# untitled.net
KiCad netlist of a schematic drawn in EAGLE
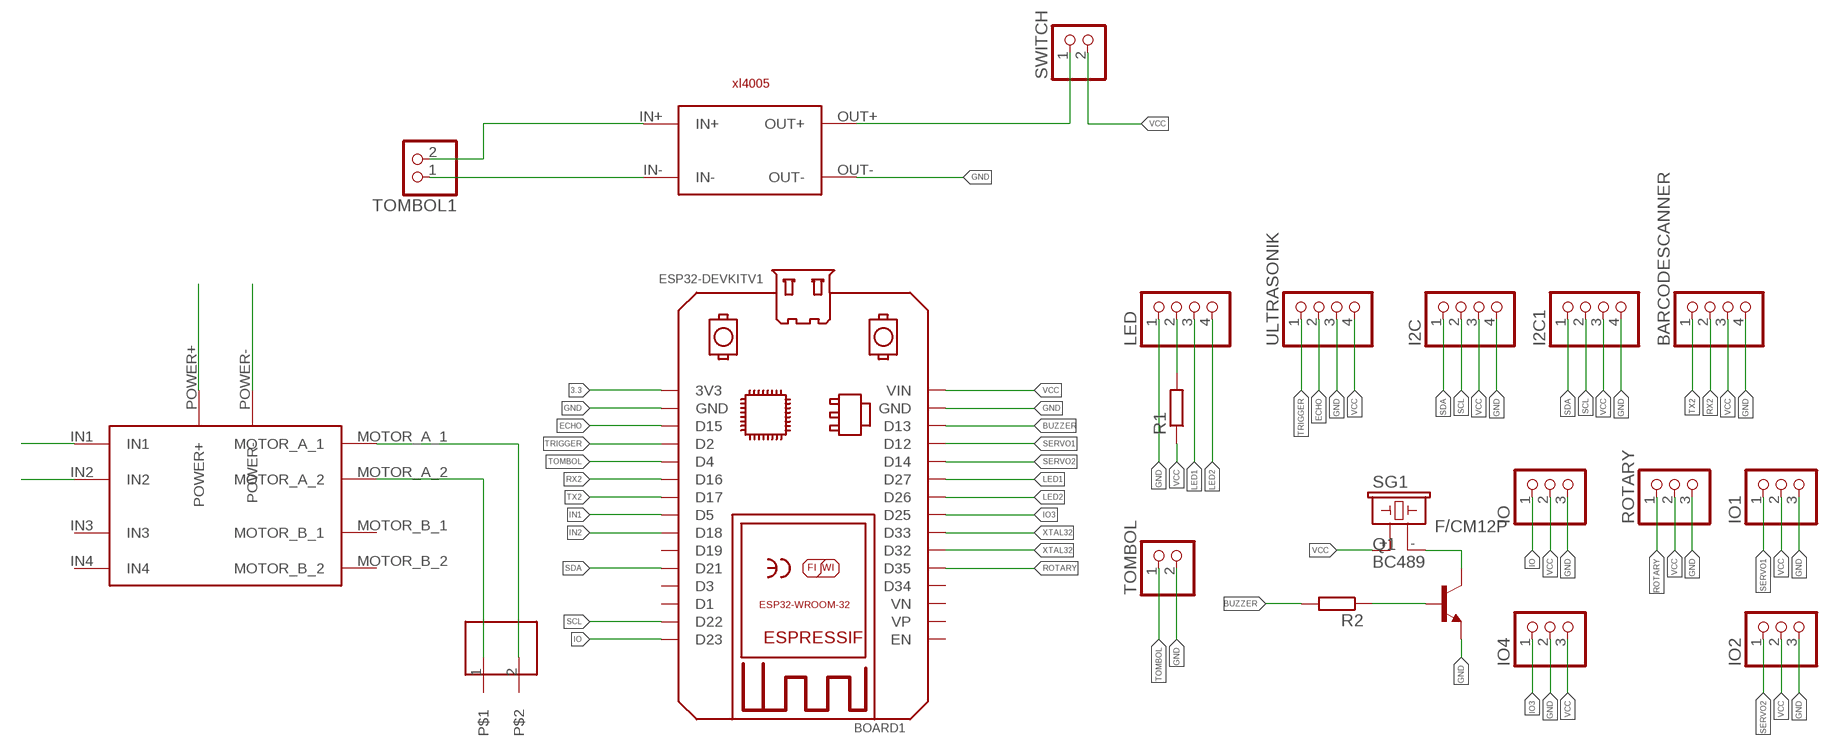
[diagram p0: schematic, sheet 1]

(export (version "E")
  (design (tool "Eeschema 10.0.6"))
  (components
    (comp (ref "BARCODESCANNER")
      (value "PINHD-1X4")
      (footprint "eagle-import:1X04")
      (libsource (lib "eagle-import") (part "PINHD-1X4"))
    )
    (comp (ref "BOARD1")
      (value "ESP32DEVKITV1SHRIDATTDUDHAT")
      (footprint "eagle-import:ESP32-DEVKITV1")
      (libsource (lib "eagle-import") (part "ESP32DEVKITV1SHRIDATTDUDHAT"))
    )
    (comp (ref "I2C")
      (value "PINHD-1X4")
      (footprint "eagle-import:1X04")
      (libsource (lib "eagle-import") (part "PINHD-1X4"))
    )
    (comp (ref "I2C1")
      (value "PINHD-1X4")
      (footprint "eagle-import:1X04")
      (libsource (lib "eagle-import") (part "PINHD-1X4"))
    )
    (comp (ref "IO")
      (value "PINHD-1X3")
      (footprint "eagle-import:1X03")
      (libsource (lib "eagle-import") (part "PINHD-1X3"))
    )
    (comp (ref "IO1")
      (value "PINHD-1X3")
      (footprint "eagle-import:1X03")
      (libsource (lib "eagle-import") (part "PINHD-1X3"))
    )
    (comp (ref "IO2")
      (value "PINHD-1X3")
      (footprint "eagle-import:1X03")
      (libsource (lib "eagle-import") (part "PINHD-1X3"))
    )
    (comp (ref "IO4")
      (value "PINHD-1X3")
      (footprint "eagle-import:1X03")
      (libsource (lib "eagle-import") (part "PINHD-1X3"))
    )
    (comp (ref "LED")
      (value "PINHD-1X4")
      (footprint "eagle-import:1X04")
      (libsource (lib "eagle-import") (part "PINHD-1X4"))
    )
    (comp (ref "Q1")
      (value "BC489")
      (footprint "eagle-import:TO92-EBC")
      (libsource (lib "eagle-import") (part "BC489"))
    )
    (comp (ref "R1")
      (value "R-EU_0207/10")
      (footprint "eagle-import:0207_10")
      (libsource (lib "eagle-import") (part "R-EU_0207/10"))
    )
    (comp (ref "R2")
      (value "R-EU_0207/10")
      (footprint "eagle-import:0207_10")
      (libsource (lib "eagle-import") (part "R-EU_0207/10"))
    )
    (comp (ref "ROTARY")
      (value "PINHD-1X3")
      (footprint "eagle-import:1X03")
      (libsource (lib "eagle-import") (part "PINHD-1X3"))
    )
    (comp (ref "SG1")
      (value "F/CM12P")
      (footprint "eagle-import:F_CM12P")
      (libsource (lib "eagle-import") (part "F/CM12P"))
    )
    (comp (ref "SWITCH")
      (value "PINHD-1X2")
      (footprint "eagle-import:1X02")
      (libsource (lib "eagle-import") (part "PINHD-1X2"))
    )
    (comp (ref "TOMBOL")
      (value "PINHD-1X2")
      (footprint "eagle-import:1X02")
      (libsource (lib "eagle-import") (part "PINHD-1X2"))
    )
    (comp (ref "TOMBOL1")
      (value "PINHD-1X2")
      (footprint "eagle-import:1X02")
      (libsource (lib "eagle-import") (part "PINHD-1X2"))
    )
    (comp (ref "U$1")
      (value "DRIVERMOTOR_MINI")
      (footprint "eagle-import:DRIVERMOTOR_MINI")
      (libsource (lib "eagle-import") (part "DRIVERMOTOR_MINI"))
    )
    (comp (ref "U$2")
      (value "DC-STEP-DOWN-XL4005")
      (footprint "eagle-import:DC-STEP-DOWN-XL4005")
      (libsource (lib "eagle-import") (part "DC-STEP-DOWN-XL4005"))
    )
    (comp (ref "U$3")
      (value "TERMINALBLOCK2")
      (footprint "eagle-import:TERMINALBLOCK2")
      (libsource (lib "eagle-import") (part "TERMINALBLOCK2"))
    )
    (comp (ref "ULTRASONIK")
      (value "PINHD-1X4")
      (footprint "eagle-import:1X04")
      (libsource (lib "eagle-import") (part "PINHD-1X4"))
    )
  )
  (nets
    (net (code "1") (name "3.3") (class "Default")
      (node (ref "BOARD1") (pin "3V3") (pinfunction "3V3_3V3") (pintype "bidirectional"))
    )
    (net (code "2") (name "BUZZER") (class "Default")
      (node (ref "BOARD1") (pin "D13") (pinfunction "D13_D13") (pintype "bidirectional"))
      (node (ref "R2") (pin "2") (pinfunction "2_2") (pintype "passive"))
    )
    (net (code "3") (name "ECHO") (class "Default")
      (node (ref "BOARD1") (pin "D15") (pinfunction "D15_D15") (pintype "bidirectional"))
      (node (ref "ULTRASONIK") (pin "2") (pinfunction "2_2") (pintype "passive"))
    )
    (net (code "4") (name "GND") (class "Default")
      (node (ref "BARCODESCANNER") (pin "4") (pinfunction "4_4") (pintype "passive"))
      (node (ref "BOARD1") (pin "GND") (pinfunction "GND_GND") (pintype "bidirectional"))
      (node (ref "BOARD1") (pin "GND@1") (pinfunction "GND_GND@1") (pintype "bidirectional"))
      (node (ref "I2C") (pin "4") (pinfunction "4_4") (pintype "passive"))
      (node (ref "I2C1") (pin "4") (pinfunction "4_4") (pintype "passive"))
      (node (ref "IO") (pin "3") (pinfunction "3_3") (pintype "passive"))
      (node (ref "IO1") (pin "3") (pinfunction "3_3") (pintype "passive"))
      (node (ref "IO2") (pin "3") (pinfunction "3_3") (pintype "passive"))
      (node (ref "IO4") (pin "2") (pinfunction "2_2") (pintype "passive"))
      (node (ref "LED") (pin "1") (pinfunction "1_1") (pintype "passive"))
      (node (ref "Q1") (pin "E") (pinfunction "E_E") (pintype "passive"))
      (node (ref "ROTARY") (pin "3") (pinfunction "3_3") (pintype "passive"))
      (node (ref "TOMBOL") (pin "2") (pinfunction "2_2") (pintype "passive"))
      (node (ref "U$1") (pin "POWER-") (pinfunction "POWER-_POWER-") (pintype "bidirectional"))
      (node (ref "U$2") (pin "OUT-") (pinfunction "OUT-_OUT-") (pintype "bidirectional"))
      (node (ref "ULTRASONIK") (pin "3") (pinfunction "3_3") (pintype "passive"))
    )
    (net (code "5") (name "IN1") (class "Default")
      (node (ref "BOARD1") (pin "D5") (pinfunction "D5_D5") (pintype "bidirectional"))
      (node (ref "U$1") (pin "IN1") (pinfunction "IN1_IN1") (pintype "bidirectional"))
    )
    (net (code "6") (name "IN2") (class "Default")
      (node (ref "BOARD1") (pin "D18") (pinfunction "D18_D18") (pintype "bidirectional"))
      (node (ref "U$1") (pin "IN2") (pinfunction "IN2_IN2") (pintype "bidirectional"))
    )
    (net (code "7") (name "IO") (class "Default")
      (node (ref "BOARD1") (pin "D23") (pinfunction "D23_D23") (pintype "bidirectional"))
      (node (ref "IO") (pin "1") (pinfunction "1_1") (pintype "passive"))
    )
    (net (code "8") (name "IO3") (class "Default")
      (node (ref "BOARD1") (pin "D25") (pinfunction "D25_D25") (pintype "bidirectional"))
      (node (ref "IO4") (pin "1") (pinfunction "1_1") (pintype "passive"))
    )
    (net (code "9") (name "LED1") (class "Default")
      (node (ref "BOARD1") (pin "D27") (pinfunction "D27_D27") (pintype "bidirectional"))
      (node (ref "LED") (pin "3") (pinfunction "3_3") (pintype "passive"))
    )
    (net (code "10") (name "LED2") (class "Default")
      (node (ref "BOARD1") (pin "D26") (pinfunction "D26_D26") (pintype "bidirectional"))
      (node (ref "LED") (pin "4") (pinfunction "4_4") (pintype "passive"))
    )
    (net (code "11") (name "Net-(LED-Pad2)") (class "Default")
      (node (ref "LED") (pin "2") (pinfunction "2_2") (pintype "passive"))
      (node (ref "R1") (pin "2") (pinfunction "2_2") (pintype "passive"))
    )
    (net (code "12") (name "Net-(Q1-PadB)") (class "Default")
      (node (ref "Q1") (pin "B") (pinfunction "B_B") (pintype "passive"))
      (node (ref "R2") (pin "1") (pinfunction "1_1") (pintype "passive"))
    )
    (net (code "13") (name "Net-(SG1-2)") (class "Default")
      (node (ref "Q1") (pin "C") (pinfunction "C_C") (pintype "passive"))
      (node (ref "SG1") (pin "-") (pinfunction "2_-") (pintype "passive"))
    )
    (net (code "14") (name "Net-(SWITCH-Pad1)") (class "Default")
      (node (ref "SWITCH") (pin "1") (pinfunction "1_1") (pintype "passive"))
      (node (ref "U$2") (pin "OUT+") (pinfunction "OUT+_OUT+") (pintype "bidirectional"))
    )
    (net (code "15") (name "Net-(TOMBOL1-Pad1)") (class "Default")
      (node (ref "TOMBOL1") (pin "1") (pinfunction "1_1") (pintype "passive"))
      (node (ref "U$2") (pin "IN-") (pinfunction "IN-_IN-") (pintype "bidirectional"))
    )
    (net (code "16") (name "Net-(TOMBOL1-Pad2)") (class "Default")
      (node (ref "TOMBOL1") (pin "2") (pinfunction "2_2") (pintype "passive"))
      (node (ref "U$2") (pin "IN+") (pinfunction "IN+_IN+") (pintype "bidirectional"))
    )
    (net (code "17") (name "Net-(U$3-P$1)") (class "Default")
      (node (ref "U$1") (pin "MOTOR_A_2") (pinfunction "MOTOR_A_2_MOTOR_A_2") (pintype "bidirectional"))
      (node (ref "U$3") (pin "1") (pinfunction "P$1_1") (pintype "bidirectional"))
    )
    (net (code "18") (name "Net-(U$3-P$2)") (class "Default")
      (node (ref "U$1") (pin "MOTOR_A_1") (pinfunction "MOTOR_A_1_MOTOR_A_1") (pintype "bidirectional"))
      (node (ref "U$3") (pin "2") (pinfunction "P$2_2") (pintype "bidirectional"))
    )
    (net (code "19") (name "ROTARY") (class "Default")
      (node (ref "BOARD1") (pin "D35") (pinfunction "D35_D35") (pintype "bidirectional"))
      (node (ref "ROTARY") (pin "1") (pinfunction "1_1") (pintype "passive"))
    )
    (net (code "20") (name "RX2") (class "Default")
      (node (ref "BARCODESCANNER") (pin "2") (pinfunction "2_2") (pintype "passive"))
      (node (ref "BOARD1") (pin "D16") (pinfunction "D16_D16") (pintype "bidirectional"))
    )
    (net (code "21") (name "SCL") (class "Default")
      (node (ref "BOARD1") (pin "D22") (pinfunction "D22_D22") (pintype "bidirectional"))
      (node (ref "I2C") (pin "2") (pinfunction "2_2") (pintype "passive"))
      (node (ref "I2C1") (pin "2") (pinfunction "2_2") (pintype "passive"))
    )
    (net (code "22") (name "SDA") (class "Default")
      (node (ref "BOARD1") (pin "D21") (pinfunction "D21_D21") (pintype "bidirectional"))
      (node (ref "I2C") (pin "1") (pinfunction "1_1") (pintype "passive"))
      (node (ref "I2C1") (pin "1") (pinfunction "1_1") (pintype "passive"))
    )
    (net (code "23") (name "SERVO1") (class "Default")
      (node (ref "BOARD1") (pin "D12") (pinfunction "D12_D12") (pintype "bidirectional"))
      (node (ref "IO1") (pin "1") (pinfunction "1_1") (pintype "passive"))
    )
    (net (code "24") (name "SERVO2") (class "Default")
      (node (ref "BOARD1") (pin "D14") (pinfunction "D14_D14") (pintype "bidirectional"))
      (node (ref "IO2") (pin "1") (pinfunction "1_1") (pintype "passive"))
    )
    (net (code "25") (name "TOMBOL") (class "Default")
      (node (ref "BOARD1") (pin "D4") (pinfunction "D4_D4") (pintype "bidirectional"))
      (node (ref "TOMBOL") (pin "1") (pinfunction "1_1") (pintype "passive"))
    )
    (net (code "26") (name "TRIGGER") (class "Default")
      (node (ref "BOARD1") (pin "D2") (pinfunction "D2_D2") (pintype "bidirectional"))
      (node (ref "ULTRASONIK") (pin "1") (pinfunction "1_1") (pintype "passive"))
    )
    (net (code "27") (name "TX2") (class "Default")
      (node (ref "BARCODESCANNER") (pin "1") (pinfunction "1_1") (pintype "passive"))
      (node (ref "BOARD1") (pin "D17") (pinfunction "D17_D17") (pintype "bidirectional"))
    )
    (net (code "28") (name "VCC") (class "Default")
      (node (ref "BARCODESCANNER") (pin "3") (pinfunction "3_3") (pintype "passive"))
      (node (ref "BOARD1") (pin "VIN") (pinfunction "VIN_VIN") (pintype "bidirectional"))
      (node (ref "I2C") (pin "3") (pinfunction "3_3") (pintype "passive"))
      (node (ref "I2C1") (pin "3") (pinfunction "3_3") (pintype "passive"))
      (node (ref "IO") (pin "2") (pinfunction "2_2") (pintype "passive"))
      (node (ref "IO1") (pin "2") (pinfunction "2_2") (pintype "passive"))
      (node (ref "IO2") (pin "2") (pinfunction "2_2") (pintype "passive"))
      (node (ref "IO4") (pin "3") (pinfunction "3_3") (pintype "passive"))
      (node (ref "R1") (pin "1") (pinfunction "1_1") (pintype "passive"))
      (node (ref "ROTARY") (pin "2") (pinfunction "2_2") (pintype "passive"))
      (node (ref "SG1") (pin "+") (pinfunction "1_+") (pintype "passive"))
      (node (ref "SWITCH") (pin "2") (pinfunction "2_2") (pintype "passive"))
      (node (ref "U$1") (pin "POWER+") (pinfunction "POWER+_POWER+") (pintype "bidirectional"))
      (node (ref "ULTRASONIK") (pin "4") (pinfunction "4_4") (pintype "passive"))
    )
    (net (code "29") (name "XTAL32") (class "Default")
      (node (ref "BOARD1") (pin "D32") (pinfunction "D32_D32") (pintype "bidirectional"))
      (node (ref "BOARD1") (pin "D33") (pinfunction "D33_D33") (pintype "bidirectional"))
    )
    (net (code "30") (name "unconnected-(BOARD1-PadD1)") (class "Default")
      (node (ref "BOARD1") (pin "D1") (pinfunction "D1_D1") (pintype "bidirectional"))
    )
    (net (code "31") (name "unconnected-(BOARD1-PadD3)") (class "Default")
      (node (ref "BOARD1") (pin "D3") (pinfunction "D3_D3") (pintype "bidirectional"))
    )
    (net (code "32") (name "unconnected-(BOARD1-PadD19)") (class "Default")
      (node (ref "BOARD1") (pin "D19") (pinfunction "D19_D19") (pintype "bidirectional"))
    )
    (net (code "33") (name "unconnected-(BOARD1-PadD34)") (class "Default")
      (node (ref "BOARD1") (pin "D34") (pinfunction "D34_D34") (pintype "bidirectional"))
    )
    (net (code "34") (name "unconnected-(BOARD1-PadEN)") (class "Default")
      (node (ref "BOARD1") (pin "EN") (pinfunction "EN_EN") (pintype "bidirectional"))
    )
    (net (code "35") (name "unconnected-(BOARD1-PadVN)") (class "Default")
      (node (ref "BOARD1") (pin "VN") (pinfunction "VN_VN") (pintype "bidirectional"))
    )
    (net (code "36") (name "unconnected-(BOARD1-PadVP)") (class "Default")
      (node (ref "BOARD1") (pin "VP") (pinfunction "VP_VP") (pintype "bidirectional"))
    )
    (net (code "37") (name "unconnected-(U$1-PadIN3)") (class "Default")
      (node (ref "U$1") (pin "IN3") (pinfunction "IN3_IN3") (pintype "bidirectional"))
    )
    (net (code "38") (name "unconnected-(U$1-PadIN4)") (class "Default")
      (node (ref "U$1") (pin "IN4") (pinfunction "IN4_IN4") (pintype "bidirectional"))
    )
    (net (code "39") (name "unconnected-(U$1-PadMOTOR_B_1)") (class "Default")
      (node (ref "U$1") (pin "MOTOR_B_1") (pinfunction "MOTOR_B_1_MOTOR_B_1") (pintype "bidirectional"))
    )
    (net (code "40") (name "unconnected-(U$1-PadMOTOR_B_2)") (class "Default")
      (node (ref "U$1") (pin "MOTOR_B_2") (pinfunction "MOTOR_B_2_MOTOR_B_2") (pintype "bidirectional"))
    )
  )
)
